# schemetic1.net
KiCad netlist of a schematic drawn in Altium Designer
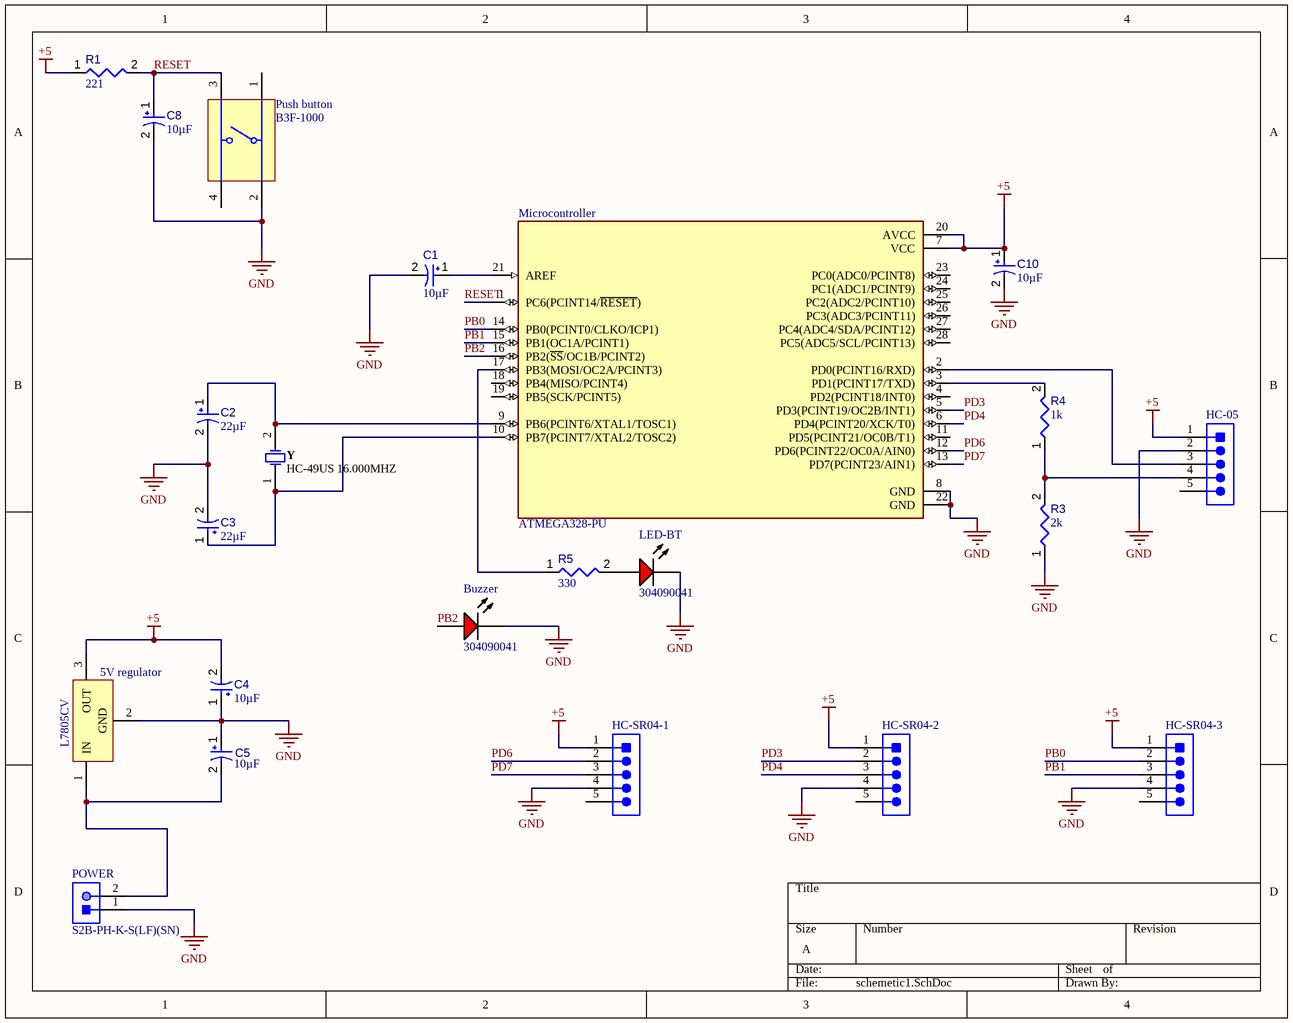
[diagram p0: schemetic1.SchDoc]

(export (version "E")
  (design (tool "Eeschema 10.0.6"))
  (components
    (comp (ref "5V regulator")
      (value "L7805CV")
      (footprint "TO220")
      (description "Positive Voltage Regulator IC, 1.5 A, 5 V, 0 to 125 degC, 3-Pin TO-220, RoHS, Tube")
      (fields (field (name "MANUFACTURER") "STMicroelectronics"))
      (libsource (lib "University of Moratuwa") (part "PM-REG-L4940-SIL3"))
    )
    (comp (ref "Buzzer")
      (value "304090041")
      (footprint "LED-2P-2.28-3MM_A")
      (description "Red LED, 80 mW, 30 mA, -25 to 85 degC, 2-Pin THD")
      (fields (field (name "MANUFACTURER") "Shenzhen CGX"))
      (libsource (lib "University of Moratuwa") (part "LED-RED-AK-2"))
    )
    (comp (ref "C1")
      (value "10µF")
      (footprint "CAPPR55-200-1100X500X1200")
      (description "Aluminum Electrolytic Capacitor, 10 uF, +/- 20%, 50 V, -40 to 85 degC, 2-Pin THD, RoHS, Bulk")
      (fields (field (name "MANUFACTURER") "Panasonic") (field (name "TOLERANCE") "20%"))
      (libsource (lib "") (part "CAP-P-2_2"))
    )
    (comp (ref "C2")
      (value "22µF")
      (footprint "CAPPR55-250-1120X630X1220")
      (description "Aluminum Electrolytic Capacitor, 22 uF, +/- 20%, 100 V, -40 to 85 degC, 2-Pin THD, RoHS, Bulk")
      (fields (field (name "MANUFACTURER") "Panasonic") (field (name "TOLERANCE") "20%"))
      (libsource (lib "") (part "CAP-P-2_1"))
    )
    (comp (ref "C3")
      (value "22µF")
      (footprint "CAPPR55-250-1120X630X1220")
      (description "Aluminum Electrolytic Capacitor, 22 uF, +/- 20%, 100 V, -40 to 85 degC, 2-Pin THD, RoHS, Bulk")
      (fields (field (name "MANUFACTURER") "Panasonic") (field (name "TOLERANCE") "20%"))
      (libsource (lib "University of Moratuwa") (part "CAP-P-2"))
    )
    (comp (ref "C4")
      (value "10µF")
      (footprint "CAPPR55-200-1100X500X1200")
      (description "Aluminum Electrolytic Capacitor, 10 uF, +/- 20%, 50 V, -40 to 85 degC, 2-Pin THD, RoHS, Bulk")
      (fields (field (name "MANUFACTURER") "Panasonic") (field (name "TOLERANCE") "20%"))
      (libsource (lib "University of Moratuwa") (part "CAP-P-2"))
    )
    (comp (ref "C5")
      (value "10µF")
      (footprint "CAPPR55-200-1100X500X1200")
      (description "Aluminum Electrolytic Capacitor, 10 uF, +/- 20%, 50 V, -40 to 85 degC, 2-Pin THD, RoHS, Bulk")
      (fields (field (name "MANUFACTURER") "Panasonic") (field (name "TOLERANCE") "20%"))
      (libsource (lib "") (part "CAP-P-2_1"))
    )
    (comp (ref "C8")
      (value "10µF")
      (footprint "CAPPR55-200-1100X500X1200")
      (description "Aluminum Electrolytic Capacitor, 10 uF, +/- 20%, 50 V, -40 to 85 degC, 2-Pin THD, RoHS, Bulk")
      (fields (field (name "MANUFACTURER") "Panasonic") (field (name "TOLERANCE") "20%"))
      (libsource (lib "") (part "CAP-P-2_1"))
    )
    (comp (ref "C10")
      (value "10µF")
      (footprint "CAPPR55-200-1100X500X1200")
      (description "Aluminum Electrolytic Capacitor, 10 uF, +/- 20%, 50 V, -40 to 85 degC, 2-Pin THD, RoHS, Bulk")
      (fields (field (name "MANUFACTURER") "Panasonic") (field (name "TOLERANCE") "20%"))
      (libsource (lib "") (part "CAP-P-2_1"))
    )
    (comp (ref "HC-05")
      (value "77311-462K05LF")
      (footprint "FCI-77311-5_V")
      (fields (field (name "MANUFACTURER") "FCI Electronics"))
      (libsource (lib "University of Moratuwa") (part "CN-1P-M-R5"))
    )
    (comp (ref "HC-SR04-1")
      (value "77311-462K05LF")
      (footprint "FCI-77311-5_V")
      (fields (field (name "MANUFACTURER") "FCI Electronics"))
      (libsource (lib "University of Moratuwa") (part "CN-1P-M-R5"))
    )
    (comp (ref "HC-SR04-2")
      (value "77311-462K05LF")
      (footprint "FCI-77311-5_V")
      (fields (field (name "MANUFACTURER") "FCI Electronics"))
      (libsource (lib "University of Moratuwa") (part "CN-1P-M-R5"))
    )
    (comp (ref "HC-SR04-3")
      (value "77311-462K05LF")
      (footprint "FCI-77311-5_V")
      (fields (field (name "MANUFACTURER") "FCI Electronics"))
      (libsource (lib "University of Moratuwa") (part "CN-1P-M-R5"))
    )
    (comp (ref "LED-BT")
      (value "304090041")
      (footprint "LED-2P-2.28-3MM_A")
      (description "Red LED, 80 mW, 30 mA, -25 to 85 degC, 2-Pin THD")
      (fields (field (name "MANUFACTURER") "Shenzhen CGX"))
      (libsource (lib "University of Moratuwa") (part "LED-RED-AK-2"))
    )
    (comp (ref "Microcontroller")
      (value "ATMEGA328-PU")
      (footprint "DIP787W46P254L3467H508Q28")
      (description "AVR AVRÂ® ATmega Microcontroller IC 8-Bit 20MHz 32KB (16K x 16) FLASH 28-PDIP")
      (fields (field (name "MF") "Microchip"))
      (libsource (lib "ATMEGA328-PU") (part "ATMEGA328-PU"))
    )
    (comp (ref "POWER")
      (value "S2B-PH-K-S(LF)(SN)")
      (footprint "JST-S2B-PH-K-S_V")
      (fields (field (name "MANUFACTURER") "Japan Solderless Terminals"))
      (libsource (lib "University of Moratuwa") (part "CN-1P-M-R2"))
    )
    (comp (ref "Push button")
      (value "B3F-1000")
      (footprint "OMRON-B3F-1000-4_V")
      (description "Tactile Switch, SPST-NO, 0.05 A, 24 V, -25 to 70 degC, 4-Pin THD, RoHS, Bulk")
      (fields (field (name "MANUFACTURER") "Omron Electronic Components"))
      (libsource (lib "University of Moratuwa") (part "SW-SPST-4_A"))
    )
    (comp (ref "R1")
      (value "221")
      (footprint "RESA60-630X240")
      (description "Axial Resistor, 221 Ohm, +/- 1%, 250 mW, -55 to 155 degC, 2-Pin THD, RoHS, Bulk")
      (fields (field (name "POWER") "250mW") (field (name "TOLERANCE") "1%"))
      (libsource (lib "University of Moratuwa") (part "RES-2"))
    )
    (comp (ref "R3")
      (value "MFR-25FBF52-1K")
      (footprint "RESA60-630X240")
      (description "Axial Resistor, 1 KOhm, +/- 1%, 250 mW, -55 to 155 degC, 2-Pin THD, RoHS, Bulk")
      (fields (field (name "TOLERANCE") "1%") (field (name "R3") "2k") (field (name "POWER") "250mW"))
      (libsource (lib "University of Moratuwa") (part "RES-2"))
    )
    (comp (ref "R4")
      (value "1k")
      (footprint "RESA60-630X240")
      (description "Axial Resistor, 1 KOhm, +/- 1%, 250 mW, -55 to 155 degC, 2-Pin THD, RoHS, Bulk")
      (fields (field (name "TOLERANCE") "1%") (field (name "POWER") "250mW"))
      (libsource (lib "University of Moratuwa") (part "RES-2"))
    )
    (comp (ref "R5")
      (value "330")
      (footprint "RESA60-630X240")
      (description "Axial Resistor, 1 KOhm, +/- 1%, 250 mW, -55 to 155 degC, 2-Pin THD, RoHS, Bulk")
      (fields (field (name "TOLERANCE") "1%") (field (name "POWER") "250mW"))
      (libsource (lib "University of Moratuwa") (part "RES-2"))
    )
    (comp (ref "Y")
      (value "HC-49US 16.000MHZ")
      (footprint "JPY-HC-49US")
      (description "Crystal, 16 MHz, +/- 30 ppm, 18 pF, -20 to 70 degC, 2-Pin THD")
      (fields (field (name "MANUFACTURER") "Jing peng yuan"))
      (libsource (lib "University of Moratuwa") (part "XTAL-1-2-2"))
    )
  )
  (nets
    (net (code "1") (name "+5") (class "Default")
      (node (ref "5V regulator") (pin "3") (pinfunction "OUT_3") (pintype "power_in"))
      (node (ref "C10") (pin "1") (pinfunction "1_1") (pintype "passive"))
      (node (ref "C4") (pin "2") (pinfunction "2_2") (pintype "passive"))
      (node (ref "HC-05") (pin "1") (pinfunction "DTR_1") (pintype "passive"))
      (node (ref "HC-SR04-1") (pin "1") (pinfunction "DTR_1") (pintype "passive"))
      (node (ref "HC-SR04-2") (pin "1") (pinfunction "DTR_1") (pintype "passive"))
      (node (ref "HC-SR04-3") (pin "1") (pinfunction "DTR_1") (pintype "passive"))
      (node (ref "Microcontroller") (pin "20") (pinfunction "AVCC_20") (pintype "power_in"))
      (node (ref "Microcontroller") (pin "7") (pinfunction "VCC_7") (pintype "power_in"))
      (node (ref "R1") (pin "1") (pinfunction "1_1") (pintype "passive"))
    )
    (net (code "2") (name "/PB0") (class "Default")
      (node (ref "HC-SR04-3") (pin "2") (pinfunction "RXI_2") (pintype "passive"))
      (node (ref "Microcontroller") (pin "14") (pinfunction "PB0(PCINT0/CLKO/ICP1)_14") (pintype "bidirectional"))
    )
    (net (code "3") (name "/PB1") (class "Default")
      (node (ref "HC-SR04-3") (pin "3") (pinfunction "TXO_3") (pintype "passive"))
      (node (ref "Microcontroller") (pin "15") (pinfunction "PB1(OC1A/PCINT1)_15") (pintype "bidirectional"))
    )
    (net (code "4") (name "/PB2") (class "Default")
      (node (ref "Buzzer") (pin "1") (pinfunction "A_1") (pintype "passive"))
      (node (ref "Microcontroller") (pin "16") (pinfunction "PB2(~{SS}/OC1B/PCINT2)_16") (pintype "bidirectional"))
    )
    (net (code "5") (name "/PD3") (class "Default")
      (node (ref "HC-SR04-2") (pin "2") (pinfunction "RXI_2") (pintype "passive"))
      (node (ref "Microcontroller") (pin "5") (pinfunction "PD3(PCINT19/OC2B/INT1)_5") (pintype "bidirectional"))
    )
    (net (code "6") (name "/PD4") (class "Default")
      (node (ref "HC-SR04-2") (pin "3") (pinfunction "TXO_3") (pintype "passive"))
      (node (ref "Microcontroller") (pin "6") (pinfunction "PD4(PCINT20/XCK/T0)_6") (pintype "bidirectional"))
    )
    (net (code "7") (name "/PD6") (class "Default")
      (node (ref "HC-SR04-1") (pin "2") (pinfunction "RXI_2") (pintype "passive"))
      (node (ref "Microcontroller") (pin "12") (pinfunction "PD6(PCINT22/OC0A/AIN0)_12") (pintype "bidirectional"))
    )
    (net (code "8") (name "/PD7") (class "Default")
      (node (ref "HC-SR04-1") (pin "3") (pinfunction "TXO_3") (pintype "passive"))
      (node (ref "Microcontroller") (pin "13") (pinfunction "PD7(PCINT23/AIN1)_13") (pintype "bidirectional"))
    )
    (net (code "9") (name "/RESET") (class "Default")
      (node (ref "C8") (pin "1") (pinfunction "1_1") (pintype "passive"))
      (node (ref "Microcontroller") (pin "1") (pinfunction "PC6(PCINT14/~{RESET})_1") (pintype "bidirectional"))
      (node (ref "Push button") (pin "3") (pinfunction "3_3") (pintype "passive"))
      (node (ref "R1") (pin "2") (pinfunction "2_2") (pintype "passive"))
    )
    (net (code "10") (name "GND") (class "Default")
      (node (ref "5V regulator") (pin "2") (pinfunction "GND_2") (pintype "power_in"))
      (node (ref "Buzzer") (pin "2") (pinfunction "K_2") (pintype "passive"))
      (node (ref "C1") (pin "2") (pinfunction "2_2") (pintype "passive"))
      (node (ref "C10") (pin "2") (pinfunction "2_2") (pintype "passive"))
      (node (ref "C2") (pin "2") (pinfunction "2_2") (pintype "passive"))
      (node (ref "C3") (pin "2") (pinfunction "2_2") (pintype "passive"))
      (node (ref "C4") (pin "1") (pinfunction "1_1") (pintype "passive"))
      (node (ref "C5") (pin "1") (pinfunction "1_1") (pintype "passive"))
      (node (ref "C8") (pin "2") (pinfunction "2_2") (pintype "passive"))
      (node (ref "HC-05") (pin "2") (pinfunction "RXI_2") (pintype "passive"))
      (node (ref "HC-SR04-1") (pin "4") (pinfunction "VCC_4") (pintype "passive"))
      (node (ref "HC-SR04-2") (pin "4") (pinfunction "VCC_4") (pintype "passive"))
      (node (ref "HC-SR04-3") (pin "4") (pinfunction "VCC_4") (pintype "passive"))
      (node (ref "LED-BT") (pin "2") (pinfunction "K_2") (pintype "passive"))
      (node (ref "Microcontroller") (pin "22") (pinfunction "GND_22") (pintype "power_in"))
      (node (ref "Microcontroller") (pin "8") (pinfunction "GND_8") (pintype "power_in"))
      (node (ref "POWER") (pin "1") (pinfunction "1_1") (pintype "passive"))
      (node (ref "Push button") (pin "2") (pinfunction "2_2") (pintype "passive"))
      (node (ref "R3") (pin "1") (pinfunction "1_1") (pintype "passive"))
    )
    (net (code "11") (name "Net-(5V regulator-IN)") (class "Default")
      (node (ref "5V regulator") (pin "1") (pinfunction "IN_1") (pintype "power_in"))
      (node (ref "C5") (pin "2") (pinfunction "2_2") (pintype "passive"))
      (node (ref "POWER") (pin "2") (pinfunction "2_2") (pintype "passive"))
    )
    (net (code "12") (name "Net-(HC-05-TXO)") (class "Default")
      (node (ref "HC-05") (pin "3") (pinfunction "TXO_3") (pintype "passive"))
      (node (ref "Microcontroller") (pin "2") (pinfunction "PD0(PCINT16/RXD)_2") (pintype "bidirectional"))
    )
    (net (code "13") (name "Net-(HC-05-VCC)") (class "Default")
      (node (ref "HC-05") (pin "4") (pinfunction "VCC_4") (pintype "passive"))
      (node (ref "R3") (pin "2") (pinfunction "2_2") (pintype "passive"))
      (node (ref "R4") (pin "1") (pinfunction "1_1") (pintype "passive"))
    )
    (net (code "14") (name "Net-(LED-BT-A)") (class "Default")
      (node (ref "LED-BT") (pin "1") (pinfunction "A_1") (pintype "passive"))
      (node (ref "R5") (pin "2") (pinfunction "2_2") (pintype "passive"))
    )
    (net (code "15") (name "Net-(Microcontroller-AREF)") (class "Default")
      (node (ref "C1") (pin "1") (pinfunction "1_1") (pintype "passive"))
      (node (ref "Microcontroller") (pin "21") (pinfunction "AREF_21") (pintype "input"))
    )
    (net (code "16") (name "Net-(Microcontroller-PB3(MOSI{slash}OC2A{slash}PCINT3))") (class "Default")
      (node (ref "Microcontroller") (pin "17") (pinfunction "PB3(MOSI/OC2A/PCINT3)_17") (pintype "bidirectional"))
      (node (ref "R5") (pin "1") (pinfunction "1_1") (pintype "passive"))
    )
    (net (code "17") (name "Net-(Microcontroller-PB6(PCINT6{slash}XTAL1{slash}TOSC1))") (class "Default")
      (node (ref "C2") (pin "1") (pinfunction "1_1") (pintype "passive"))
      (node (ref "Microcontroller") (pin "9") (pinfunction "PB6(PCINT6/XTAL1/TOSC1)_9") (pintype "bidirectional"))
      (node (ref "Y") (pin "2") (pinfunction "2_2") (pintype "passive"))
    )
    (net (code "18") (name "Net-(Microcontroller-PB7(PCINT7{slash}XTAL2{slash}TOSC2))") (class "Default")
      (node (ref "C3") (pin "1") (pinfunction "1_1") (pintype "passive"))
      (node (ref "Microcontroller") (pin "10") (pinfunction "PB7(PCINT7/XTAL2/TOSC2)_10") (pintype "bidirectional"))
      (node (ref "Y") (pin "1") (pinfunction "1_1") (pintype "passive"))
    )
    (net (code "19") (name "Net-(Microcontroller-PD1(PCINT17{slash}TXD))") (class "Default")
      (node (ref "Microcontroller") (pin "3") (pinfunction "PD1(PCINT17/TXD)_3") (pintype "bidirectional"))
      (node (ref "R4") (pin "2") (pinfunction "2_2") (pintype "passive"))
    )
    (net (code "20") (name "unconnected-(HC-05-CTS-Pad5)") (class "Default")
      (node (ref "HC-05") (pin "5") (pinfunction "CTS_5") (pintype "passive"))
    )
    (net (code "21") (name "unconnected-(HC-SR04-1-CTS-Pad5)") (class "Default")
      (node (ref "HC-SR04-1") (pin "5") (pinfunction "CTS_5") (pintype "passive"))
    )
    (net (code "22") (name "unconnected-(HC-SR04-2-CTS-Pad5)") (class "Default")
      (node (ref "HC-SR04-2") (pin "5") (pinfunction "CTS_5") (pintype "passive"))
    )
    (net (code "23") (name "unconnected-(HC-SR04-3-CTS-Pad5)") (class "Default")
      (node (ref "HC-SR04-3") (pin "5") (pinfunction "CTS_5") (pintype "passive"))
    )
    (net (code "24") (name "unconnected-(Microcontroller-PB4(MISO{slash}PCINT4)-Pad18)") (class "Default")
      (node (ref "Microcontroller") (pin "18") (pinfunction "PB4(MISO/PCINT4)_18") (pintype "bidirectional"))
    )
    (net (code "25") (name "unconnected-(Microcontroller-PB5(SCK{slash}PCINT5)-Pad19)") (class "Default")
      (node (ref "Microcontroller") (pin "19") (pinfunction "PB5(SCK/PCINT5)_19") (pintype "bidirectional"))
    )
    (net (code "26") (name "unconnected-(Microcontroller-PC0(ADC0{slash}PCINT8)-Pad23)") (class "Default")
      (node (ref "Microcontroller") (pin "23") (pinfunction "PC0(ADC0/PCINT8)_23") (pintype "bidirectional"))
    )
    (net (code "27") (name "unconnected-(Microcontroller-PC1(ADC1{slash}PCINT9)-Pad24)") (class "Default")
      (node (ref "Microcontroller") (pin "24") (pinfunction "PC1(ADC1/PCINT9)_24") (pintype "bidirectional"))
    )
    (net (code "28") (name "unconnected-(Microcontroller-PC2(ADC2{slash}PCINT10)-Pad25)") (class "Default")
      (node (ref "Microcontroller") (pin "25") (pinfunction "PC2(ADC2/PCINT10)_25") (pintype "bidirectional"))
    )
    (net (code "29") (name "unconnected-(Microcontroller-PC3(ADC3{slash}PCINT11)-Pad26)") (class "Default")
      (node (ref "Microcontroller") (pin "26") (pinfunction "PC3(ADC3/PCINT11)_26") (pintype "bidirectional"))
    )
    (net (code "30") (name "unconnected-(Microcontroller-PC4(ADC4{slash}SDA{slash}PCINT12)-Pad27)") (class "Default")
      (node (ref "Microcontroller") (pin "27") (pinfunction "PC4(ADC4/SDA/PCINT12)_27") (pintype "bidirectional"))
    )
    (net (code "31") (name "unconnected-(Microcontroller-PC5(ADC5{slash}SCL{slash}PCINT13)-Pad28)") (class "Default")
      (node (ref "Microcontroller") (pin "28") (pinfunction "PC5(ADC5/SCL/PCINT13)_28") (pintype "bidirectional"))
    )
    (net (code "32") (name "unconnected-(Microcontroller-PD2(PCINT18{slash}INT0)-Pad4)") (class "Default")
      (node (ref "Microcontroller") (pin "4") (pinfunction "PD2(PCINT18/INT0)_4") (pintype "bidirectional"))
    )
    (net (code "33") (name "unconnected-(Microcontroller-PD5(PCINT21{slash}OC0B{slash}T1)-Pad11)") (class "Default")
      (node (ref "Microcontroller") (pin "11") (pinfunction "PD5(PCINT21/OC0B/T1)_11") (pintype "bidirectional"))
    )
    (net (code "34") (name "unconnected-(Push button-Pad1)") (class "Default")
      (node (ref "Push button") (pin "1") (pinfunction "1_1") (pintype "passive"))
    )
    (net (code "35") (name "unconnected-(Push button-Pad4)") (class "Default")
      (node (ref "Push button") (pin "4") (pinfunction "4_4") (pintype "passive"))
    )
  )
)
